# MelansonTech_Boost_PSU_IsolatedShuntAmp_.net
KiCad netlist of a schematic drawn in Altium Designer
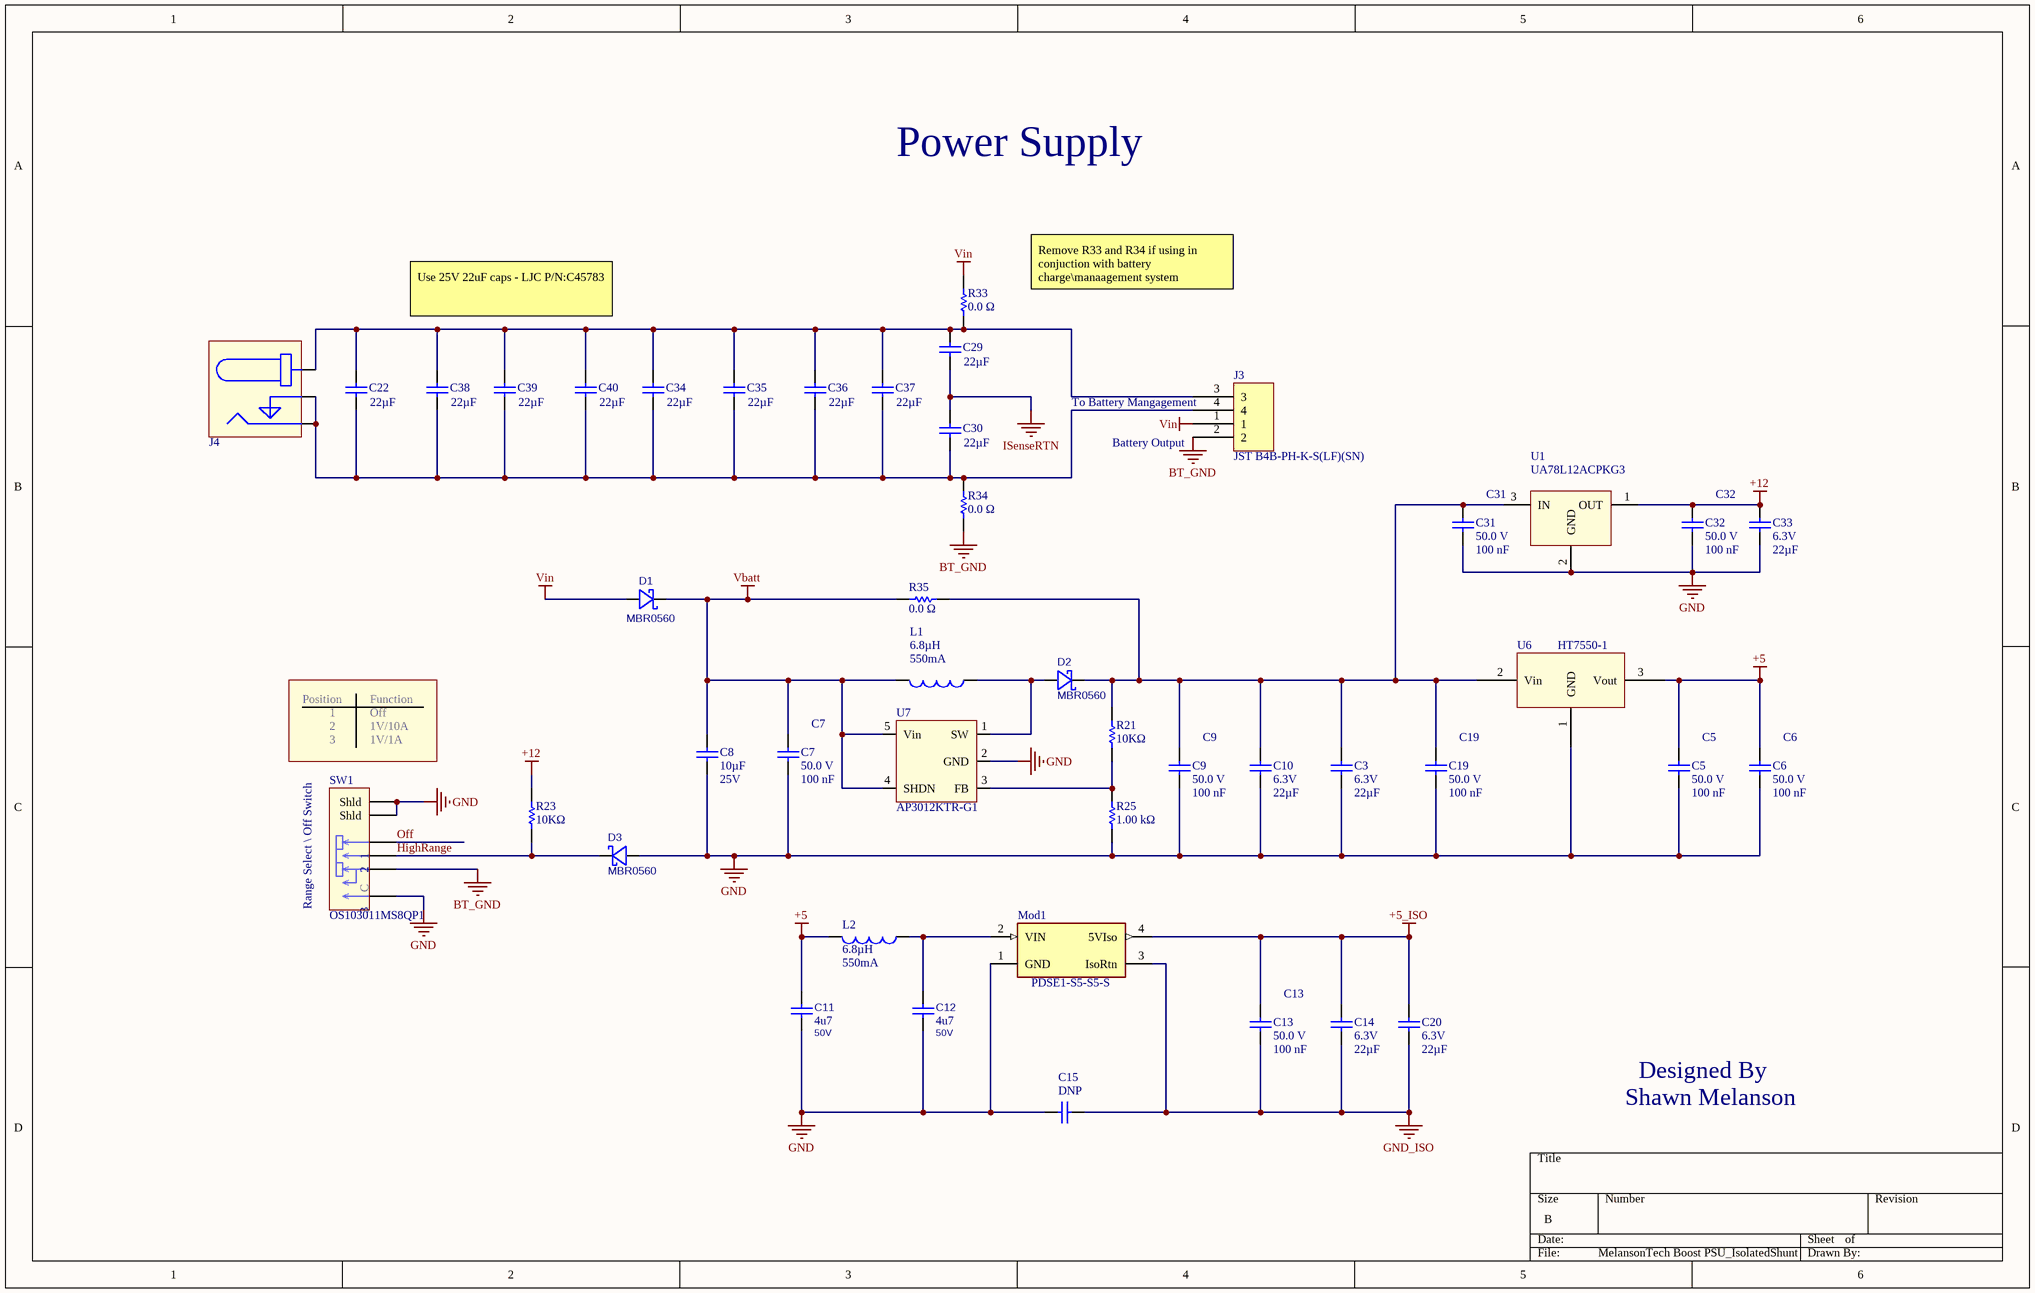
[diagram p0: MelansonTech Boost PSU_IsolatedShuntAmp tmp.SchDoc]

(export (version "E")
  (design (tool "Eeschema 10.0.6"))
  (components
    (comp (ref "C3")
      (value "CL21A226MQQNNNE")
      (footprint "Cap,0805")
      (description "CAP CER 22UF 6.3V X5R 0805")
      (fields
        (field (name "MANUFACTURER") "Samsung Electro-Mechanics")
        (field (name "TOLERANCE") "±20%")
        (field (name "VOLTAGE - RATED") "6.3V")
        (field (name "CAPACITANCE") "22µF")
      )
      (libsource (lib "Master Mar2021") (part "Cap,0805,22uF,6.3V,X5R,±20%,CL21A226MQQNNNE"))
    )
    (comp (ref "C5")
      (value "CC0805KRX7R9BB104")
      (footprint "Cap,0805")
      (description "CAP CER 0.1UF 50V X7R 0805")
      (fields
        (field (name "VOLTAGE RATING (DC)") "50.0 V")
        (field (name "CAPACITANCE") "100 nF")
        (field (name "MANUFACTURER") "YAGEO")
      )
      (libsource (lib "Master Mar2024") (part "Cap,0805,100nf,50V,5%,CC0805KRX7R9BB104"))
    )
    (comp (ref "C6")
      (value "CC0805KRX7R9BB104")
      (footprint "Cap,0805")
      (description "CAP CER 0.1UF 50V X7R 0805")
      (fields
        (field (name "VOLTAGE RATING (DC)") "50.0 V")
        (field (name "CAPACITANCE") "100 nF")
        (field (name "MANUFACTURER") "YAGEO")
      )
      (libsource (lib "Master Mar2024") (part "Cap,0805,100nf,50V,5%,CC0805KRX7R9BB104"))
    )
    (comp (ref "C7")
      (value "CC0805KRX7R9BB104")
      (footprint "CAP, 0805, HD")
      (description "CAP CER 0.1UF 50V X7R 0805")
      (fields
        (field (name "VOLTAGE RATING (DC)") "50.0 V")
        (field (name "CAPACITANCE") "100 nF")
        (field (name "MANUFACTURER") "YAGEO")
      )
      (libsource (lib "Master Mar2024") (part "Cap,0805,100nf,50V,5%,CC0805KRX7R9BB104"))
    )
    (comp (ref "C8")
      (value "C3216X7R1E106K160AB")
      (footprint "Cap, 1206")
      (description "10µF ±10% 25V Ceramic Capacitor X7R 1206 (3216 Metric)")
      (fields
        (field (name "MANUFACTURER") "TDK Corporation")
        (field (name "TOLERANCE") "±10%")
        (field (name "CAPACITANCE") "10µF")
        (field (name "VOLTAGE - RATED") "25V")
      )
      (libsource (lib "Master DEC 2020") (part "CAP,1206,10uF,25V,C3216X7R1E106K160AB"))
    )
    (comp (ref "C9")
      (value "CC0805KRX7R9BB104")
      (footprint "CAP, 0805, HD")
      (description "CAP CER 0.1UF 50V X7R 0805")
      (fields
        (field (name "VOLTAGE RATING (DC)") "50.0 V")
        (field (name "CAPACITANCE") "100 nF")
        (field (name "MANUFACTURER") "YAGEO")
      )
      (libsource (lib "Master Mar2024") (part "Cap,0805,100nf,50V,5%,CC0805KRX7R9BB104"))
    )
    (comp (ref "C10")
      (value "CL21A226MQQNNNE")
      (footprint "Cap,0805")
      (description "CAP CER 22UF 6.3V X5R 0805")
      (fields
        (field (name "MANUFACTURER") "Samsung Electro-Mechanics")
        (field (name "TOLERANCE") "±20%")
        (field (name "VOLTAGE - RATED") "6.3V")
        (field (name "CAPACITANCE") "22µF")
      )
      (libsource (lib "Master Mar2021") (part "Cap,0805,22uF,6.3V,X5R,±20%,CL21A226MQQNNNE"))
    )
    (comp (ref "C11")
      (value "CL31B475KBHNNNE")
      (footprint "Cap, 1206")
      (description "Cap,SMD,MLCC,4u7,50V,X7R,10%,1206")
      (fields
        (field (name "MANUFACTURER") "Samsung")
        (field (name "TOLERANCE") "10%")
        (field (name "CAPACITANCE") "4u7")
        (field (name "VOLTAGE") "50V")
      )
      (libsource (lib "Master JULY2019") (part "Cap,1206,4.7uF,10%,50V,CL31B475KBHNNNE"))
    )
    (comp (ref "C12")
      (value "CL31B475KBHNNNE")
      (footprint "Cap, 1206")
      (description "Cap,SMD,MLCC,4u7,50V,X7R,10%,1206")
      (fields
        (field (name "MANUFACTURER") "Samsung")
        (field (name "TOLERANCE") "10%")
        (field (name "CAPACITANCE") "4u7")
        (field (name "VOLTAGE") "50V")
      )
      (libsource (lib "Master JULY2019") (part "Cap,1206,4.7uF,10%,50V,CL31B475KBHNNNE"))
    )
    (comp (ref "C13")
      (value "CC0805KRX7R9BB104")
      (footprint "Cap,0805")
      (description "CAP CER 0.1UF 50V X7R 0805")
      (fields
        (field (name "VOLTAGE RATING (DC)") "50.0 V")
        (field (name "CAPACITANCE") "100 nF")
        (field (name "MANUFACTURER") "YAGEO")
      )
      (libsource (lib "Master Mar2024") (part "Cap,0805,100nf,50V,5%,CC0805KRX7R9BB104"))
    )
    (comp (ref "C14")
      (value "CL21A226MQQNNNE")
      (footprint "Cap,0805")
      (description "CAP CER 22UF 6.3V X5R 0805")
      (fields
        (field (name "MANUFACTURER") "Samsung Electro-Mechanics")
        (field (name "TOLERANCE") "±20%")
        (field (name "VOLTAGE - RATED") "6.3V")
        (field (name "CAPACITANCE") "22µF")
      )
      (libsource (lib "Master Mar2021") (part "Cap,0805,22uF,6.3V,X5R,±20%,CL21A226MQQNNNE"))
    )
    (comp (ref "C15")
      (value "S102K33Y5PP63K5R")
      (footprint "Cap, 5mm Lead Spaceing, 4mm dai")
      (description "CAP CER 1000PF 2KV Y5P RADIAL")
      (fields (field (name "MANUFACTURER") "Vishay BC Components") (field (name "TOLERANCE") "±10%"))
      (libsource (lib "Master JULY2019") (part "Cap,TH,Ceramic,5mm Spacing,1nF,2kV, S102K33Y5PP63K5R"))
    )
    (comp (ref "C19")
      (value "CC0805KRX7R9BB104")
      (footprint "Cap,0805")
      (description "CAP CER 0.1UF 50V X7R 0805")
      (fields
        (field (name "VOLTAGE RATING (DC)") "50.0 V")
        (field (name "CAPACITANCE") "100 nF")
        (field (name "MANUFACTURER") "YAGEO")
      )
      (libsource (lib "Master Mar2024") (part "Cap,0805,100nf,50V,5%,CC0805KRX7R9BB104"))
    )
    (comp (ref "C20")
      (value "CL21A226MQQNNNE")
      (footprint "Cap,0805")
      (description "CAP CER 22UF 6.3V X5R 0805")
      (fields
        (field (name "MANUFACTURER") "Samsung Electro-Mechanics")
        (field (name "TOLERANCE") "±20%")
        (field (name "VOLTAGE - RATED") "6.3V")
        (field (name "CAPACITANCE") "22µF")
      )
      (libsource (lib "Master Mar2021") (part "Cap,0805,22uF,6.3V,X5R,±20%,CL21A226MQQNNNE"))
    )
    (comp (ref "C22")
      (value "CL21A226MQQNNNE")
      (footprint "Cap,0805")
      (description "CAP CER 22UF 6.3V X5R 0805")
      (fields
        (field (name "MANUFACTURER") "Samsung Electro-Mechanics")
        (field (name "TOLERANCE") "±20%")
        (field (name "CAPACITANCE") "22µF")
      )
      (libsource (lib "Master Mar2021") (part "Cap,0805,22uF,6.3V,X5R,±20%,CL21A226MQQNNNE"))
    )
    (comp (ref "C29")
      (value "CL21A226MQQNNNE")
      (footprint "Cap,0805")
      (description "CAP CER 22UF 6.3V X5R 0805")
      (fields
        (field (name "MANUFACTURER") "Samsung Electro-Mechanics")
        (field (name "TOLERANCE") "±20%")
        (field (name "CAPACITANCE") "22µF")
      )
      (libsource (lib "Master Mar2021") (part "Cap,0805,22uF,6.3V,X5R,±20%,CL21A226MQQNNNE"))
    )
    (comp (ref "C30")
      (value "CL21A226MQQNNNE")
      (footprint "Cap,0805")
      (description "CAP CER 22UF 6.3V X5R 0805")
      (fields
        (field (name "MANUFACTURER") "Samsung Electro-Mechanics")
        (field (name "TOLERANCE") "±20%")
        (field (name "CAPACITANCE") "22µF")
      )
      (libsource (lib "Master Mar2021") (part "Cap,0805,22uF,6.3V,X5R,±20%,CL21A226MQQNNNE"))
    )
    (comp (ref "C31")
      (value "CC0805KRX7R9BB104")
      (footprint "Cap,0805")
      (description "CAP CER 0.1UF 50V X7R 0805")
      (fields
        (field (name "VOLTAGE RATING (DC)") "50.0 V")
        (field (name "CAPACITANCE") "100 nF")
        (field (name "MANUFACTURER") "YAGEO")
      )
      (libsource (lib "Master Mar2024") (part "Cap,0805,100nf,50V,5%,CC0805KRX7R9BB104"))
    )
    (comp (ref "C32")
      (value "CC0805KRX7R9BB104")
      (footprint "Cap,0805")
      (description "CAP CER 0.1UF 50V X7R 0805")
      (fields
        (field (name "VOLTAGE RATING (DC)") "50.0 V")
        (field (name "CAPACITANCE") "100 nF")
        (field (name "MANUFACTURER") "YAGEO")
      )
      (libsource (lib "Master Mar2024") (part "Cap,0805,100nf,50V,5%,CC0805KRX7R9BB104"))
    )
    (comp (ref "C33")
      (value "CL21A226MQQNNNE")
      (footprint "Cap,0805")
      (description "CAP CER 22UF 6.3V X5R 0805")
      (fields
        (field (name "MANUFACTURER") "Samsung Electro-Mechanics")
        (field (name "TOLERANCE") "±20%")
        (field (name "VOLTAGE - RATED") "6.3V")
        (field (name "CAPACITANCE") "22µF")
      )
      (libsource (lib "Master Mar2021") (part "Cap,0805,22uF,6.3V,X5R,±20%,CL21A226MQQNNNE"))
    )
    (comp (ref "C34")
      (value "CL21A226MQQNNNE")
      (footprint "Cap,0805")
      (description "CAP CER 22UF 6.3V X5R 0805")
      (fields
        (field (name "MANUFACTURER") "Samsung Electro-Mechanics")
        (field (name "TOLERANCE") "±20%")
        (field (name "CAPACITANCE") "22µF")
      )
      (libsource (lib "Master Mar2021") (part "Cap,0805,22uF,6.3V,X5R,±20%,CL21A226MQQNNNE"))
    )
    (comp (ref "C35")
      (value "CL21A226MQQNNNE")
      (footprint "Cap,0805")
      (description "CAP CER 22UF 6.3V X5R 0805")
      (fields
        (field (name "MANUFACTURER") "Samsung Electro-Mechanics")
        (field (name "TOLERANCE") "±20%")
        (field (name "CAPACITANCE") "22µF")
      )
      (libsource (lib "Master Mar2021") (part "Cap,0805,22uF,6.3V,X5R,±20%,CL21A226MQQNNNE"))
    )
    (comp (ref "C36")
      (value "CL21A226MQQNNNE")
      (footprint "Cap,0805")
      (description "CAP CER 22UF 6.3V X5R 0805")
      (fields
        (field (name "MANUFACTURER") "Samsung Electro-Mechanics")
        (field (name "TOLERANCE") "±20%")
        (field (name "CAPACITANCE") "22µF")
      )
      (libsource (lib "Master Mar2021") (part "Cap,0805,22uF,6.3V,X5R,±20%,CL21A226MQQNNNE"))
    )
    (comp (ref "C37")
      (value "CL21A226MQQNNNE")
      (footprint "Cap,0805")
      (description "CAP CER 22UF 6.3V X5R 0805")
      (fields
        (field (name "MANUFACTURER") "Samsung Electro-Mechanics")
        (field (name "TOLERANCE") "±20%")
        (field (name "CAPACITANCE") "22µF")
      )
      (libsource (lib "Master Mar2021") (part "Cap,0805,22uF,6.3V,X5R,±20%,CL21A226MQQNNNE"))
    )
    (comp (ref "C38")
      (value "CL21A226MQQNNNE")
      (footprint "Cap,0805")
      (description "CAP CER 22UF 6.3V X5R 0805")
      (fields
        (field (name "MANUFACTURER") "Samsung Electro-Mechanics")
        (field (name "TOLERANCE") "±20%")
        (field (name "CAPACITANCE") "22µF")
      )
      (libsource (lib "Master Mar2021") (part "Cap,0805,22uF,6.3V,X5R,±20%,CL21A226MQQNNNE"))
    )
    (comp (ref "C39")
      (value "CL21A226MQQNNNE")
      (footprint "Cap,0805")
      (description "CAP CER 22UF 6.3V X5R 0805")
      (fields
        (field (name "MANUFACTURER") "Samsung Electro-Mechanics")
        (field (name "TOLERANCE") "±20%")
        (field (name "CAPACITANCE") "22µF")
      )
      (libsource (lib "Master Mar2021") (part "Cap,0805,22uF,6.3V,X5R,±20%,CL21A226MQQNNNE"))
    )
    (comp (ref "C40")
      (value "CL21A226MQQNNNE")
      (footprint "Cap,0805")
      (description "CAP CER 22UF 6.3V X5R 0805")
      (fields
        (field (name "MANUFACTURER") "Samsung Electro-Mechanics")
        (field (name "TOLERANCE") "±20%")
        (field (name "CAPACITANCE") "22µF")
      )
      (libsource (lib "Master Mar2021") (part "Cap,0805,22uF,6.3V,X5R,±20%,CL21A226MQQNNNE"))
    )
    (comp (ref "D1")
      (value "MBR0560")
      (footprint "SOD123")
      (description "Dio,Sig,Schtky,0.5A,60V,SOD123")
      (fields (field (name "MANUFACTURER") "MCC") (field (name "VOLTAGE") "60V"))
      (libsource (lib "Master DEC 2020") (part "Diode,SOD123,Shottky,60V,0.5A,MBR0560"))
    )
    (comp (ref "D2")
      (value "MBR0560")
      (footprint "SOD123")
      (description "Dio,Sig,Schtky,0.5A,60V,SOD123")
      (fields (field (name "MANUFACTURER") "MCC") (field (name "VOLTAGE") "60V"))
      (libsource (lib "Master DEC 2020") (part "Diode,SOD123,Shottky,60V,0.5A,MBR0560"))
    )
    (comp (ref "D3")
      (value "MBR0560")
      (footprint "SOD123")
      (description "Dio,Sig,Schtky,0.5A,60V,SOD123")
      (fields (field (name "MANUFACTURER") "MCC") (field (name "VOLTAGE") "60V"))
      (libsource (lib "Master DEC 2020") (part "Diode,SOD123,Shottky,60V,0.5A,MBR0560"))
    )
    (comp (ref "J3")
      (value "JST B4B-PH-K-S(LF)(SN)")
      (footprint "Conn, JST, 4 pin, 2mm spacing Right Angle")
      (description "PH Series 4 Position 2 mm Pitch Through Hole Crimp Top Entry Shrouded Header")
      (fields (field (name "MANUFACTURER PART NUMBER") "B4B-PH-K-S(LF)(SN)"))
      (libsource (lib "Master Nov2021") (part "Conntector, though hole, JST, 4pin, 2mm,B4B-PH-K-S(LF)(SN)"))
    )
    (comp (ref "J4")
      (value "PJ-002A")
      (footprint "Connector,Barrel,2.1mm,5.5mm,DC power Jack")
      (description "Power Barrel Connector Jack 2.10mm ID (0.083\"), 5.50mm OD (0.217\") Through Hole, Right Angle")
      (fields (field (name "MANUFACTURER") "CUI Inc."))
      (libsource (lib "Master Nov2021") (part "Connector,Barrel,ID 2.1mm,OD 5.5mm,Power Connect, PJ-002A"))
    )
    (comp (ref "L1")
      (value "MLZ2012N6R8LT000")
      (footprint "Ind, 0805")
      (description "FIXED IND 6.8UH 550MA 250 MOHM")
      (fields
        (field (name "MANUFACTURER") "TDK Corporation")
        (field (name "TOLERANCE") "±20%")
        (field (name "INDUCTANCE") "6.8µH")
        (field (name "CURRENT RATING (AMPS)") "550mA")
      )
      (libsource (lib "Master DEC 2020") (part "Ind,0805,6.8uH,550mA,0.25Ω, MLZ2012N6R8LT000"))
    )
    (comp (ref "L2")
      (value "MLZ2012N6R8LT000")
      (footprint "Ind, 0805")
      (description "FIXED IND 6.8UH 550MA 250 MOHM")
      (fields
        (field (name "MANUFACTURER") "TDK Corporation")
        (field (name "TOLERANCE") "±20%")
        (field (name "INDUCTANCE") "6.8µH")
        (field (name "CURRENT RATING (AMPS)") "550mA")
      )
      (libsource (lib "Master JULY2019") (part "Ind,0805,6.8uH,550mA,0.25Ω, MLZ2012N6R8LT000"))
    )
    (comp (ref "Mod1")
      (value "PDSE1-S5-S5-S")
      (footprint "CONV_PDSE1-S5-S5-S")
      (description "DC-DC ISOLATED, 1 W, 4.5-5.5 VDC")
      (fields (field (name "MANUFACTURER") "CUI Inc."))
      (libsource (lib "Master JULY2019") (part "Mod,PSU,4.5-5.5Vin,5Vout,1W, PDSE1-S5-S5-S"))
    )
    (comp (ref "R21")
      (value "Vishay / Dale CRCW080510K0FKTA")
      (footprint "res, 0805, HD")
      (description "RES SMD 10K OHM 1% 1/8W 0805")
      (fields (field (name "RESISTANCE") "10KΩ"))
      (libsource (lib "Master Mar2021") (part "Res,0805,10.0kΩ,1%,100 ppm,CRCW080510K0FKTA"))
    )
    (comp (ref "R23")
      (value "Vishay / Dale CRCW080510K0FKTA")
      (footprint "res, 0805, HD")
      (description "RES SMD 10K OHM 1% 1/8W 0805")
      (fields (field (name "RESISTANCE") "10KΩ"))
      (libsource (lib "Master JULY2019") (part "Res,0805,10.0kΩ,1%,100 ppm,CRCW080510K0FKTA"))
    )
    (comp (ref "R25")
      (value "Vishay CRCW08051K00JNEA")
      (footprint "res, 0805, HD")
      (description "Res Thick Film 0805 1K Ohm 5% 0.125W(1/8W) ±200ppm/C Molded SMD Automotive Paper T/R")
      (fields
        (field (name "MANUFACTURER PART NUMBER") "CRCW08051K00JNEA")
        (field (name "RESISTANCE") "1.00 kΩ")
      )
      (libsource (lib "Master DEC 2020") (part "Res,0805,1.00 kΩ,5%,200ppm,CRCW08051K00JNEA"))
    )
    (comp (ref "R33")
      (value "CR0805-J/-000ELF")
      (footprint "res, 0805, HD")
      (description "RES SMD 0 OHM JUMPER 1/8W 0805")
      (fields
        (field (name "TOLERANCE") "Jumper")
        (field (name "BASE PART NUMBER") "CR0805")
        (field (name "RESISTANCE") "0.0 Ω")
      )
      (libsource (lib "Master Nov2021") (part "Res,0805,0.0Ω,150V, CR0805-J/-000ELF"))
    )
    (comp (ref "R34")
      (value "CR0805-J/-000ELF")
      (footprint "res, 0805, HD")
      (description "RES SMD 0 OHM JUMPER 1/8W 0805")
      (fields
        (field (name "TOLERANCE") "Jumper")
        (field (name "BASE PART NUMBER") "CR0805")
        (field (name "RESISTANCE") "0.0 Ω")
      )
      (libsource (lib "Master Nov2021") (part "Res,0805,0.0Ω,150V, CR0805-J/-000ELF"))
    )
    (comp (ref "R35")
      (value "CR0805-J/-000ELF")
      (footprint "res, 0805, HD")
      (description "RES SMD 0 OHM JUMPER 1/8W 0805")
      (fields
        (field (name "TOLERANCE") "Jumper")
        (field (name "BASE PART NUMBER") "CR0805")
        (field (name "RESISTANCE") "0.0 Ω")
      )
      (libsource (lib "Master Nov2021") (part "Res,0805,0.0Ω,150V, CR0805-J/-000ELF"))
    )
    (comp (ref "SW1")
      (value "OS103011MS8QP1")
      (footprint "Switch,Slide,.SP3T, OS103011 -Side")
      (description "SWITCH SLIDE SP3T 100MA 12V")
      (fields (field (name "MANUFACTURER") "C&K"))
      (libsource (lib "Master Nov2021") (part "Switch,TH,Slide,SP3T,100MA,12V,OS103011MS8QP1"))
    )
    (comp (ref "U1")
      (value "UA78L12ACPKG3")
      (footprint "SOT89-3")
      (description "IC REG LINEAR 12V 100MA SOT89-3")
      (fields (field (name "MANUFACTURER") "Texas Instruments"))
      (libsource (lib "Master Nov2021") (part "Reg,Linear,Pos,Fixed,12Vout,27Vin,100mA,UA78L12ACPKG3"))
    )
    (comp (ref "U6")
      (value "HT7550-1")
      (footprint "SOT89-3")
      (description "LOW DROPOUT REGULATORS(LDO) POSITIVE FIXED 55MV @ 1MA 30V 5V 150MA SOT-89(SOT-89-3) ROHS")
      (fields
        (field (name "LCSC PART #") "C16106")
        (field (name "MANUFACTURER") "Holtek Semicon")
        (field (name "MFG P/N") "HT7550-1")
      )
      (libsource (lib "Master DEC 2020") (part "Reg,Linear,Fixed,SOT-89-3,30Vin,5Vout,150mA,HT7550-1"))
    )
    (comp (ref "U7")
      (value "AP3012KTR-G1")
      (footprint "SOT23-5")
      (description "IC REG BOOST ADJ 500MA SOT23-5")
      (fields (field (name "MANUFACTURER") "Diodes Incorporated") (field (name "MFG P/N") "AP3012KTR-G1"))
      (libsource (lib "Master DEC 2020") (part "Reg,Switching,Boost,2.6-16Vin,29Vout,0.5A, AP3012KTR-G1"))
    )
  )
  (nets
    (net (code "1") (name "+5") (class "Default")
      (node (ref "C11") (pin "2") (pintype "passive"))
      (node (ref "C5") (pin "2") (pinfunction "2_2") (pintype "passive"))
      (node (ref "C6") (pin "2") (pinfunction "2_2") (pintype "passive"))
      (node (ref "L2") (pin "2") (pinfunction "2_2") (pintype "passive"))
      (node (ref "U6") (pin "3") (pinfunction "Vout_3") (pintype "passive"))
    )
    (net (code "2") (name "+5_ISO") (class "Default")
      (node (ref "C13") (pin "2") (pinfunction "2_2") (pintype "passive"))
      (node (ref "C14") (pin "2") (pinfunction "2_2") (pintype "passive"))
      (node (ref "C20") (pin "2") (pinfunction "2_2") (pintype "passive"))
      (node (ref "Mod1") (pin "4") (pinfunction "5VIso_4") (pintype "output"))
    )
    (net (code "3") (name "+12") (class "Default")
      (node (ref "C32") (pin "2") (pinfunction "2_2") (pintype "passive"))
      (node (ref "C33") (pin "2") (pinfunction "2_2") (pintype "passive"))
      (node (ref "R23") (pin "1") (pinfunction "1_1") (pintype "passive"))
      (node (ref "U1") (pin "1") (pinfunction "OUT_1") (pintype "passive"))
    )
    (net (code "4") (name "/HighRange") (class "Default")
      (node (ref "D3") (pin "1") (pinfunction "C_1") (pintype "passive"))
      (node (ref "R23") (pin "2") (pinfunction "2_2") (pintype "passive"))
      (node (ref "SW1") (pin "3") (pinfunction "3_3") (pintype "passive"))
    )
    (net (code "5") (name "/Off") (class "Default")
      (node (ref "SW1") (pin "4") (pinfunction "4_4") (pintype "passive"))
    )
    (net (code "6") (name "BT_GND") (class "Default")
      (node (ref "J3") (pin "2") (pinfunction "2_2") (pintype "passive"))
      (node (ref "R34") (pin "2") (pinfunction "2_2") (pintype "passive"))
      (node (ref "SW1") (pin "2") (pinfunction "2_2") (pintype "passive"))
    )
    (net (code "7") (name "GND") (class "Default")
      (node (ref "C10") (pin "1") (pinfunction "1_1") (pintype "passive"))
      (node (ref "C11") (pin "1") (pintype "passive"))
      (node (ref "C12") (pin "1") (pintype "passive"))
      (node (ref "C15") (pin "2") (pinfunction "2_2") (pintype "passive"))
      (node (ref "C19") (pin "1") (pinfunction "1_1") (pintype "passive"))
      (node (ref "C3") (pin "1") (pinfunction "1_1") (pintype "passive"))
      (node (ref "C31") (pin "1") (pinfunction "1_1") (pintype "passive"))
      (node (ref "C32") (pin "1") (pinfunction "1_1") (pintype "passive"))
      (node (ref "C33") (pin "1") (pinfunction "1_1") (pintype "passive"))
      (node (ref "C5") (pin "1") (pinfunction "1_1") (pintype "passive"))
      (node (ref "C6") (pin "1") (pinfunction "1_1") (pintype "passive"))
      (node (ref "C7") (pin "1") (pinfunction "1_1") (pintype "passive"))
      (node (ref "C8") (pin "1") (pinfunction "1_1") (pintype "passive"))
      (node (ref "C9") (pin "1") (pinfunction "1_1") (pintype "passive"))
      (node (ref "D3") (pin "2") (pinfunction "A_2") (pintype "passive"))
      (node (ref "Mod1") (pin "1") (pinfunction "GND_1") (pintype "power_in"))
      (node (ref "R25") (pin "2") (pinfunction "2_2") (pintype "passive"))
      (node (ref "SW1") (pin "1") (pinfunction "1_1") (pintype "passive"))
      (node (ref "SW1") (pin "5") (pinfunction "Shld_5") (pintype "passive"))
      (node (ref "SW1") (pin "6") (pinfunction "Shld_6") (pintype "passive"))
      (node (ref "U1") (pin "2") (pinfunction "GND_2") (pintype "passive"))
      (node (ref "U6") (pin "1") (pinfunction "GND_1") (pintype "passive"))
      (node (ref "U7") (pin "2") (pinfunction "GND_2") (pintype "passive"))
    )
    (net (code "8") (name "GND_ISO") (class "Default")
      (node (ref "C13") (pin "1") (pinfunction "1_1") (pintype "passive"))
      (node (ref "C14") (pin "1") (pinfunction "1_1") (pintype "passive"))
      (node (ref "C15") (pin "1") (pinfunction "1_1") (pintype "passive"))
      (node (ref "C20") (pin "1") (pinfunction "1_1") (pintype "passive"))
      (node (ref "Mod1") (pin "3") (pinfunction "IsoRtn_3") (pintype "power_in"))
    )
    (net (code "9") (name "ISenseRTN") (class "Default")
      (node (ref "C29") (pin "1") (pinfunction "1_1") (pintype "passive"))
      (node (ref "C30") (pin "2") (pinfunction "2_2") (pintype "passive"))
    )
    (net (code "10") (name "Net-(C22-Pad1)") (class "Default")
      (node (ref "C22") (pin "1") (pinfunction "1_1") (pintype "passive"))
      (node (ref "C30") (pin "1") (pinfunction "1_1") (pintype "passive"))
      (node (ref "C34") (pin "1") (pinfunction "1_1") (pintype "passive"))
      (node (ref "C35") (pin "1") (pinfunction "1_1") (pintype "passive"))
      (node (ref "C36") (pin "1") (pinfunction "1_1") (pintype "passive"))
      (node (ref "C37") (pin "1") (pinfunction "1_1") (pintype "passive"))
      (node (ref "C38") (pin "1") (pinfunction "1_1") (pintype "passive"))
      (node (ref "C39") (pin "1") (pinfunction "1_1") (pintype "passive"))
      (node (ref "C40") (pin "1") (pinfunction "1_1") (pintype "passive"))
      (node (ref "J3") (pin "4") (pinfunction "4_4") (pintype "passive"))
      (node (ref "J4") (pin "2") (pinfunction "2_2") (pintype "passive"))
      (node (ref "J4") (pin "3") (pinfunction "3_3") (pintype "passive"))
      (node (ref "R34") (pin "1") (pinfunction "1_1") (pintype "passive"))
    )
    (net (code "11") (name "Net-(C22-Pad2)") (class "Default")
      (node (ref "C22") (pin "2") (pinfunction "2_2") (pintype "passive"))
      (node (ref "C29") (pin "2") (pinfunction "2_2") (pintype "passive"))
      (node (ref "C34") (pin "2") (pinfunction "2_2") (pintype "passive"))
      (node (ref "C35") (pin "2") (pinfunction "2_2") (pintype "passive"))
      (node (ref "C36") (pin "2") (pinfunction "2_2") (pintype "passive"))
      (node (ref "C37") (pin "2") (pinfunction "2_2") (pintype "passive"))
      (node (ref "C38") (pin "2") (pinfunction "2_2") (pintype "passive"))
      (node (ref "C39") (pin "2") (pinfunction "2_2") (pintype "passive"))
      (node (ref "C40") (pin "2") (pinfunction "2_2") (pintype "passive"))
      (node (ref "J3") (pin "3") (pinfunction "3_3") (pintype "passive"))
      (node (ref "J4") (pin "1") (pinfunction "1_1") (pintype "passive"))
      (node (ref "R33") (pin "2") (pinfunction "2_2") (pintype "passive"))
    )
    (net (code "12") (name "Net-(D2-A)") (class "Default")
      (node (ref "D2") (pin "2") (pinfunction "A_2") (pintype "passive"))
      (node (ref "L1") (pin "1") (pinfunction "1_1") (pintype "passive"))
      (node (ref "U7") (pin "1") (pinfunction "SW_1") (pintype "passive"))
    )
    (net (code "13") (name "Net-(D2-C)") (class "Default")
      (node (ref "C10") (pin "2") (pinfunction "2_2") (pintype "passive"))
      (node (ref "C19") (pin "2") (pinfunction "2_2") (pintype "passive"))
      (node (ref "C3") (pin "2") (pinfunction "2_2") (pintype "passive"))
      (node (ref "C31") (pin "2") (pinfunction "2_2") (pintype "passive"))
      (node (ref "C9") (pin "2") (pinfunction "2_2") (pintype "passive"))
      (node (ref "D2") (pin "1") (pinfunction "C_1") (pintype "passive"))
      (node (ref "R21") (pin "2") (pinfunction "2_2") (pintype "passive"))
      (node (ref "R35") (pin "2") (pinfunction "2_2") (pintype "passive"))
      (node (ref "U1") (pin "3") (pinfunction "IN_3") (pintype "passive"))
      (node (ref "U6") (pin "2") (pinfunction "Vin_2") (pintype "passive"))
    )
    (net (code "14") (name "Net-(Mod1-VIN)") (class "Default")
      (node (ref "C12") (pin "2") (pintype "passive"))
      (node (ref "L2") (pin "1") (pinfunction "1_1") (pintype "passive"))
      (node (ref "Mod1") (pin "2") (pinfunction "VIN_2") (pintype "input"))
    )
    (net (code "15") (name "Net-(U7-FB)") (class "Default")
      (node (ref "R21") (pin "1") (pinfunction "1_1") (pintype "passive"))
      (node (ref "R25") (pin "1") (pinfunction "1_1") (pintype "passive"))
      (node (ref "U7") (pin "3") (pinfunction "FB_3") (pintype "passive"))
    )
    (net (code "16") (name "Vbatt") (class "Default")
      (node (ref "C7") (pin "2") (pinfunction "2_2") (pintype "passive"))
      (node (ref "C8") (pin "2") (pinfunction "2_2") (pintype "passive"))
      (node (ref "D1") (pin "1") (pinfunction "C_1") (pintype "passive"))
      (node (ref "L1") (pin "2") (pinfunction "2_2") (pintype "passive"))
      (node (ref "R35") (pin "1") (pinfunction "1_1") (pintype "passive"))
      (node (ref "U7") (pin "4") (pinfunction "SHDN_4") (pintype "passive"))
      (node (ref "U7") (pin "5") (pinfunction "Vin_5") (pintype "passive"))
    )
    (net (code "17") (name "Vin") (class "Default")
      (node (ref "D1") (pin "2") (pinfunction "A_2") (pintype "passive"))
      (node (ref "J3") (pin "1") (pinfunction "1_1") (pintype "passive"))
      (node (ref "R33") (pin "1") (pinfunction "1_1") (pintype "passive"))
    )
  )
)
